# B115A.net
KiCad netlist of a schematic drawn in EAGLE
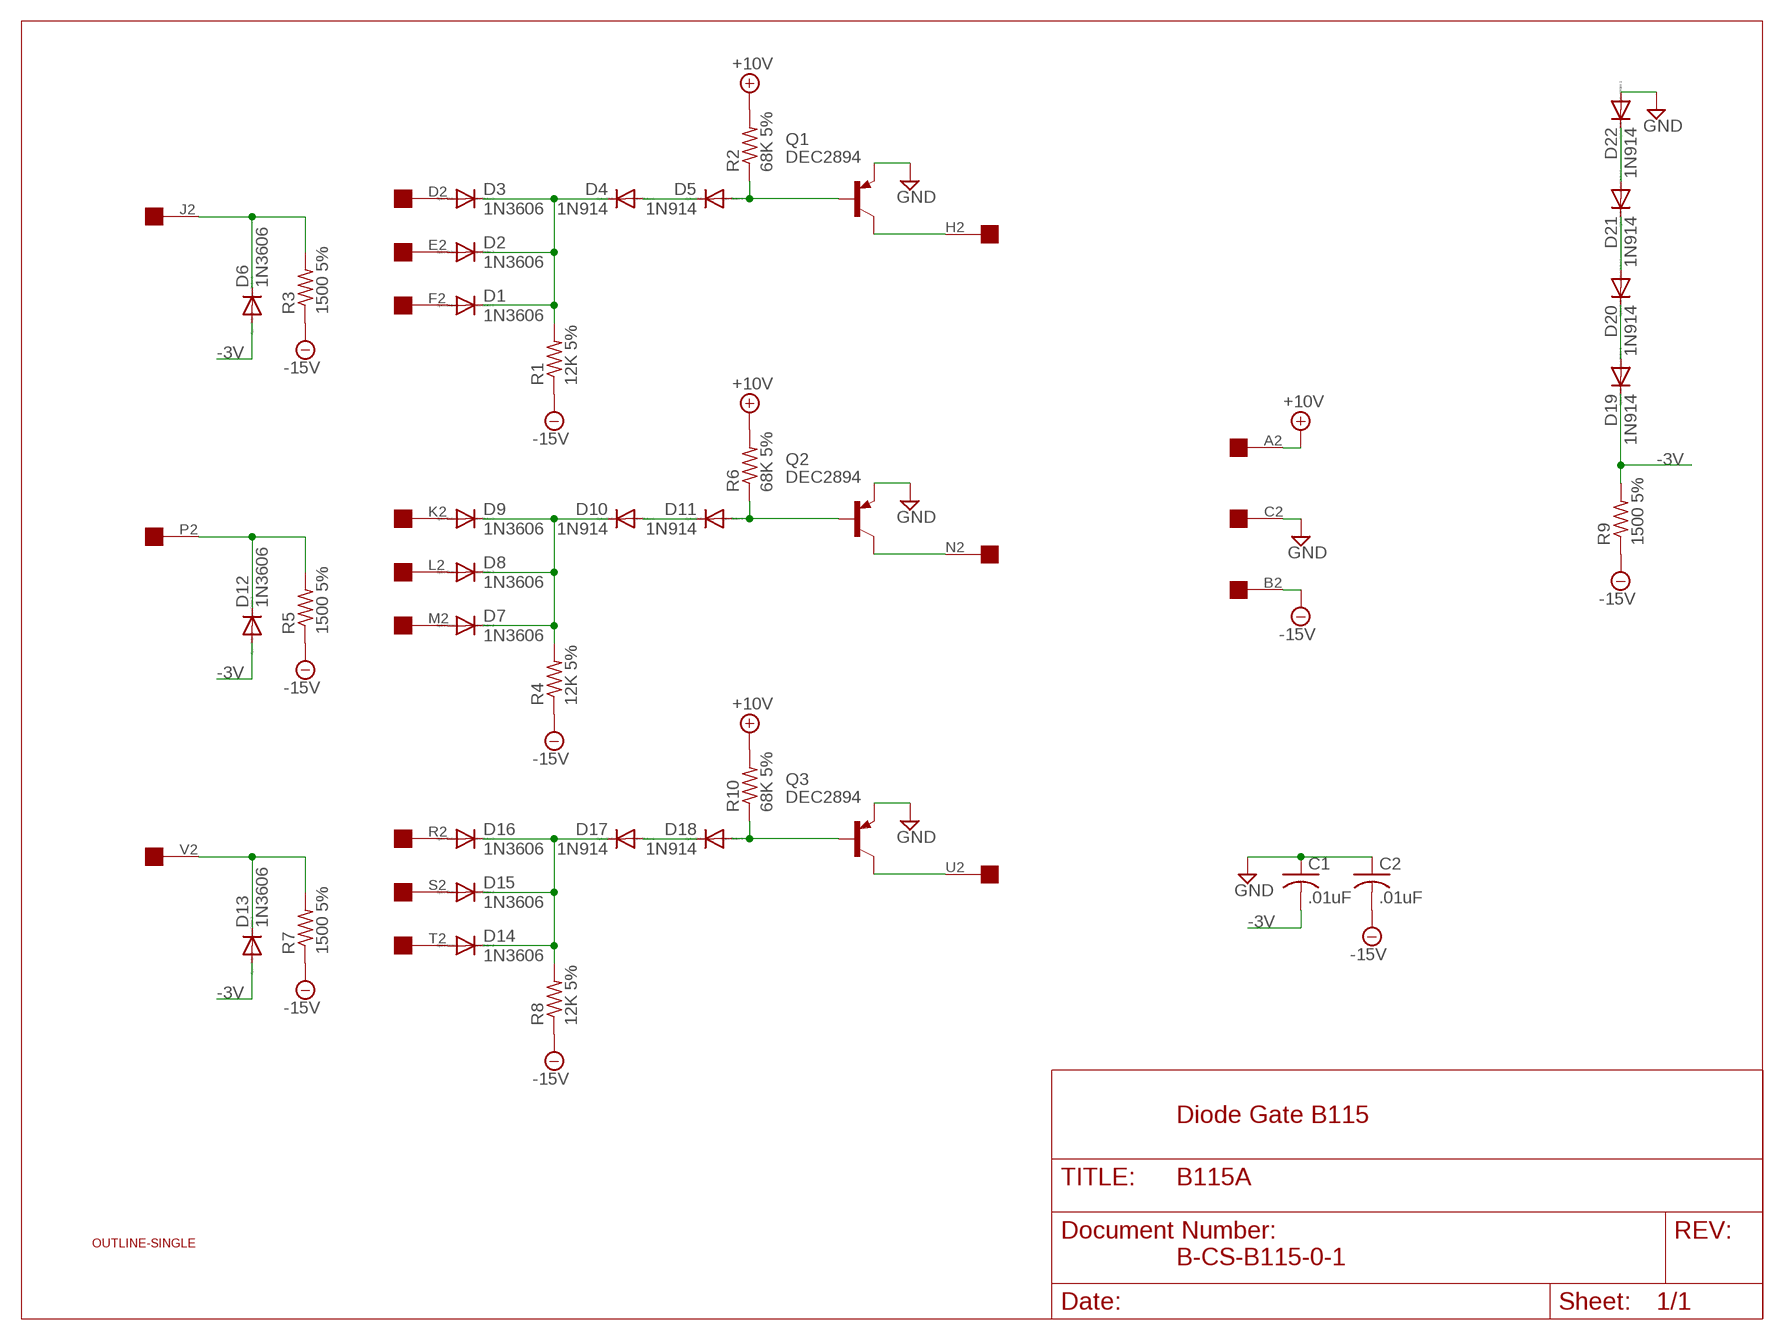
[diagram p0: schematic, sheet 1]

(export (version "E")
  (design (tool "Eeschema 10.0.6"))
  (components
    (comp (ref "C1")
      (value ".01uF")
      (footprint "eagle-import:C050-025X075")
      (libsource (lib "eagle-import") (part "C-US050-025X075"))
    )
    (comp (ref "C2")
      (value ".01uF")
      (footprint "eagle-import:C050-025X075")
      (libsource (lib "eagle-import") (part "C-US050-025X075"))
    )
    (comp (ref "D1")
      (value "1N3606")
      (footprint "eagle-import:DO35-10")
      (libsource (lib "eagle-import") (part "1N4148DO35-10"))
    )
    (comp (ref "D2")
      (value "1N3606")
      (footprint "eagle-import:DO35-10")
      (libsource (lib "eagle-import") (part "1N4148DO35-10"))
    )
    (comp (ref "D3")
      (value "1N3606")
      (footprint "eagle-import:DO35-10")
      (libsource (lib "eagle-import") (part "1N4148DO35-10"))
    )
    (comp (ref "D4")
      (value "1N914")
      (footprint "eagle-import:DO35-10")
      (libsource (lib "eagle-import") (part "1N4148DO35-10"))
    )
    (comp (ref "D5")
      (value "1N914")
      (footprint "eagle-import:DO35-10")
      (libsource (lib "eagle-import") (part "1N4148DO35-10"))
    )
    (comp (ref "D6")
      (value "1N3606")
      (footprint "eagle-import:DO35-10")
      (libsource (lib "eagle-import") (part "1N4148DO35-10"))
    )
    (comp (ref "D7")
      (value "1N3606")
      (footprint "eagle-import:DO35-10")
      (libsource (lib "eagle-import") (part "1N4148DO35-10"))
    )
    (comp (ref "D8")
      (value "1N3606")
      (footprint "eagle-import:DO35-10")
      (libsource (lib "eagle-import") (part "1N4148DO35-10"))
    )
    (comp (ref "D9")
      (value "1N3606")
      (footprint "eagle-import:DO35-10")
      (libsource (lib "eagle-import") (part "1N4148DO35-10"))
    )
    (comp (ref "D10")
      (value "1N914")
      (footprint "eagle-import:DO35-10")
      (libsource (lib "eagle-import") (part "1N4148DO35-10"))
    )
    (comp (ref "D11")
      (value "1N914")
      (footprint "eagle-import:DO35-10")
      (libsource (lib "eagle-import") (part "1N4148DO35-10"))
    )
    (comp (ref "D12")
      (value "1N3606")
      (footprint "eagle-import:DO35-10")
      (libsource (lib "eagle-import") (part "1N4148DO35-10"))
    )
    (comp (ref "D13")
      (value "1N3606")
      (footprint "eagle-import:DO35-10")
      (libsource (lib "eagle-import") (part "1N4148DO35-10"))
    )
    (comp (ref "D14")
      (value "1N3606")
      (footprint "eagle-import:DO35-10")
      (libsource (lib "eagle-import") (part "1N4148DO35-10"))
    )
    (comp (ref "D15")
      (value "1N3606")
      (footprint "eagle-import:DO35-10")
      (libsource (lib "eagle-import") (part "1N4148DO35-10"))
    )
    (comp (ref "D16")
      (value "1N3606")
      (footprint "eagle-import:DO35-10")
      (libsource (lib "eagle-import") (part "1N4148DO35-10"))
    )
    (comp (ref "D17")
      (value "1N914")
      (footprint "eagle-import:DO35-10")
      (libsource (lib "eagle-import") (part "1N4148DO35-10"))
    )
    (comp (ref "D18")
      (value "1N914")
      (footprint "eagle-import:DO35-10")
      (libsource (lib "eagle-import") (part "1N4148DO35-10"))
    )
    (comp (ref "D19")
      (value "1N914")
      (footprint "eagle-import:DO35-10")
      (libsource (lib "eagle-import") (part "1N4148DO35-10"))
    )
    (comp (ref "D20")
      (value "1N914")
      (footprint "eagle-import:DO35-10")
      (libsource (lib "eagle-import") (part "1N4148DO35-10"))
    )
    (comp (ref "D21")
      (value "1N914")
      (footprint "eagle-import:DO35-10")
      (libsource (lib "eagle-import") (part "1N4148DO35-10"))
    )
    (comp (ref "D22")
      (value "1N914")
      (footprint "eagle-import:DO35-10")
      (libsource (lib "eagle-import") (part "1N4148DO35-10"))
    )
    (comp (ref "Q1")
      (value "DEC2894")
      (footprint "eagle-import:TO39")
      (libsource (lib "eagle-import") (part "2N2904"))
    )
    (comp (ref "Q2")
      (value "DEC2894")
      (footprint "eagle-import:TO39")
      (libsource (lib "eagle-import") (part "2N2904"))
    )
    (comp (ref "Q3")
      (value "DEC2894")
      (footprint "eagle-import:TO39")
      (libsource (lib "eagle-import") (part "2N2904"))
    )
    (comp (ref "R1")
      (value "12K 5%")
      (footprint "eagle-import:0207_10")
      (libsource (lib "eagle-import") (part "R-US_0207/10"))
    )
    (comp (ref "R2")
      (value "68K 5%")
      (footprint "eagle-import:0207_10")
      (libsource (lib "eagle-import") (part "R-US_0207/10"))
    )
    (comp (ref "R3")
      (value "1500 5%")
      (footprint "eagle-import:0207_10")
      (libsource (lib "eagle-import") (part "R-US_0207/10"))
    )
    (comp (ref "R4")
      (value "12K 5%")
      (footprint "eagle-import:0207_10")
      (libsource (lib "eagle-import") (part "R-US_0207/10"))
    )
    (comp (ref "R5")
      (value "1500 5%")
      (footprint "eagle-import:0207_10")
      (libsource (lib "eagle-import") (part "R-US_0207/10"))
    )
    (comp (ref "R6")
      (value "68K 5%")
      (footprint "eagle-import:0207_10")
      (libsource (lib "eagle-import") (part "R-US_0207/10"))
    )
    (comp (ref "R7")
      (value "1500 5%")
      (footprint "eagle-import:0207_10")
      (libsource (lib "eagle-import") (part "R-US_0207/10"))
    )
    (comp (ref "R8")
      (value "12K 5%")
      (footprint "eagle-import:0207_10")
      (libsource (lib "eagle-import") (part "R-US_0207/10"))
    )
    (comp (ref "R9")
      (value "1500 5%")
      (footprint "eagle-import:0207_10")
      (libsource (lib "eagle-import") (part "R-US_0207/10"))
    )
    (comp (ref "R10")
      (value "68K 5%")
      (footprint "eagle-import:0207_10")
      (libsource (lib "eagle-import") (part "R-US_0207/10"))
    )
    (comp (ref "U$1")
      (value "OUTLINE-SINGLE")
      (footprint "eagle-import:SINGLE")
      (libsource (lib "eagle-import") (part "OUTLINE-SINGLE"))
    )
    (comp (ref "U$2")
      (value "EDGE-1")
      (footprint "eagle-import:EDGE-CON1")
      (libsource (lib "eagle-import") (part "EDGE-1"))
    )
  )
  (nets
    (net (code "1") (name "+10V") (class "Default")
      (node (ref "R10") (pin "2") (pinfunction "2_2") (pintype "passive"))
      (node (ref "R2") (pin "2") (pinfunction "2_2") (pintype "passive"))
      (node (ref "R6") (pin "2") (pinfunction "2_2") (pintype "passive"))
      (node (ref "U$2") (pin "A2") (pinfunction "1_A2") (pintype "bidirectional"))
    )
    (net (code "2") (name "-15V") (class "Default")
      (node (ref "C2") (pin "2") (pinfunction "2_2") (pintype "passive"))
      (node (ref "R1") (pin "1") (pinfunction "1_1") (pintype "passive"))
      (node (ref "R3") (pin "1") (pinfunction "1_1") (pintype "passive"))
      (node (ref "R4") (pin "1") (pinfunction "1_1") (pintype "passive"))
      (node (ref "R5") (pin "1") (pinfunction "1_1") (pintype "passive"))
      (node (ref "R7") (pin "1") (pinfunction "1_1") (pintype "passive"))
      (node (ref "R8") (pin "1") (pinfunction "1_1") (pintype "passive"))
      (node (ref "R9") (pin "1") (pinfunction "1_1") (pintype "passive"))
      (node (ref "U$2") (pin "B2") (pinfunction "1_B2") (pintype "bidirectional"))
    )
    (net (code "3") (name "/-3V") (class "Default")
      (node (ref "C1") (pin "2") (pinfunction "2_2") (pintype "passive"))
      (node (ref "D12") (pin "A") (pinfunction "A_A") (pintype "passive"))
      (node (ref "D13") (pin "A") (pinfunction "A_A") (pintype "passive"))
      (node (ref "D19") (pin "C") (pinfunction "C_C") (pintype "passive"))
      (node (ref "D6") (pin "A") (pinfunction "A_A") (pintype "passive"))
      (node (ref "R9") (pin "2") (pinfunction "2_2") (pintype "passive"))
    )
    (net (code "4") (name "GND") (class "Default")
      (node (ref "C1") (pin "1") (pinfunction "1_1") (pintype "passive"))
      (node (ref "C2") (pin "1") (pinfunction "1_1") (pintype "passive"))
      (node (ref "D22") (pin "A") (pinfunction "A_A") (pintype "passive"))
      (node (ref "Q1") (pin "1") (pinfunction "E_1") (pintype "passive"))
      (node (ref "Q2") (pin "1") (pinfunction "E_1") (pintype "passive"))
      (node (ref "Q3") (pin "1") (pinfunction "E_1") (pintype "passive"))
      (node (ref "U$2") (pin "C2") (pinfunction "1_C2") (pintype "bidirectional"))
    )
    (net (code "5") (name "Net-(D1-PadC)") (class "Default")
      (node (ref "D1") (pin "C") (pinfunction "C_C") (pintype "passive"))
      (node (ref "D2") (pin "C") (pinfunction "C_C") (pintype "passive"))
      (node (ref "D3") (pin "C") (pinfunction "C_C") (pintype "passive"))
      (node (ref "D4") (pin "C") (pinfunction "C_C") (pintype "passive"))
      (node (ref "R1") (pin "2") (pinfunction "2_2") (pintype "passive"))
    )
    (net (code "6") (name "Net-(D4-PadA)") (class "Default")
      (node (ref "D4") (pin "A") (pinfunction "A_A") (pintype "passive"))
      (node (ref "D5") (pin "C") (pinfunction "C_C") (pintype "passive"))
    )
    (net (code "7") (name "Net-(D10-PadA)") (class "Default")
      (node (ref "D10") (pin "A") (pinfunction "A_A") (pintype "passive"))
      (node (ref "D11") (pin "C") (pinfunction "C_C") (pintype "passive"))
    )
    (net (code "8") (name "Net-(D10-PadC)") (class "Default")
      (node (ref "D10") (pin "C") (pinfunction "C_C") (pintype "passive"))
      (node (ref "D7") (pin "C") (pinfunction "C_C") (pintype "passive"))
      (node (ref "D8") (pin "C") (pinfunction "C_C") (pintype "passive"))
      (node (ref "D9") (pin "C") (pinfunction "C_C") (pintype "passive"))
      (node (ref "R4") (pin "2") (pinfunction "2_2") (pintype "passive"))
    )
    (net (code "9") (name "Net-(D14-PadC)") (class "Default")
      (node (ref "D14") (pin "C") (pinfunction "C_C") (pintype "passive"))
      (node (ref "D15") (pin "C") (pinfunction "C_C") (pintype "passive"))
      (node (ref "D16") (pin "C") (pinfunction "C_C") (pintype "passive"))
      (node (ref "D17") (pin "C") (pinfunction "C_C") (pintype "passive"))
      (node (ref "R8") (pin "2") (pinfunction "2_2") (pintype "passive"))
    )
    (net (code "10") (name "Net-(D17-PadA)") (class "Default")
      (node (ref "D17") (pin "A") (pinfunction "A_A") (pintype "passive"))
      (node (ref "D18") (pin "C") (pinfunction "C_C") (pintype "passive"))
    )
    (net (code "11") (name "Net-(D19-PadA)") (class "Default")
      (node (ref "D19") (pin "A") (pinfunction "A_A") (pintype "passive"))
      (node (ref "D20") (pin "C") (pinfunction "C_C") (pintype "passive"))
    )
    (net (code "12") (name "Net-(D20-PadA)") (class "Default")
      (node (ref "D20") (pin "A") (pinfunction "A_A") (pintype "passive"))
      (node (ref "D21") (pin "C") (pinfunction "C_C") (pintype "passive"))
    )
    (net (code "13") (name "Net-(D21-PadA)") (class "Default")
      (node (ref "D21") (pin "A") (pinfunction "A_A") (pintype "passive"))
      (node (ref "D22") (pin "C") (pinfunction "C_C") (pintype "passive"))
    )
    (net (code "14") (name "Net-(Q1-B)") (class "Default")
      (node (ref "D5") (pin "A") (pinfunction "A_A") (pintype "passive"))
      (node (ref "Q1") (pin "2") (pinfunction "B_2") (pintype "passive"))
      (node (ref "R2") (pin "1") (pinfunction "1_1") (pintype "passive"))
    )
    (net (code "15") (name "Net-(Q1-C)") (class "Default")
      (node (ref "Q1") (pin "3") (pinfunction "C_3") (pintype "passive"))
      (node (ref "U$2") (pin "H2") (pinfunction "1_H2") (pintype "bidirectional"))
    )
    (net (code "16") (name "Net-(Q2-B)") (class "Default")
      (node (ref "D11") (pin "A") (pinfunction "A_A") (pintype "passive"))
      (node (ref "Q2") (pin "2") (pinfunction "B_2") (pintype "passive"))
      (node (ref "R6") (pin "1") (pinfunction "1_1") (pintype "passive"))
    )
    (net (code "17") (name "Net-(Q2-C)") (class "Default")
      (node (ref "Q2") (pin "3") (pinfunction "C_3") (pintype "passive"))
      (node (ref "U$2") (pin "N2") (pinfunction "1_N2") (pintype "bidirectional"))
    )
    (net (code "18") (name "Net-(Q3-B)") (class "Default")
      (node (ref "D18") (pin "A") (pinfunction "A_A") (pintype "passive"))
      (node (ref "Q3") (pin "2") (pinfunction "B_2") (pintype "passive"))
      (node (ref "R10") (pin "1") (pinfunction "1_1") (pintype "passive"))
    )
    (net (code "19") (name "Net-(Q3-C)") (class "Default")
      (node (ref "Q3") (pin "3") (pinfunction "C_3") (pintype "passive"))
      (node (ref "U$2") (pin "U2") (pinfunction "1_U2") (pintype "bidirectional"))
    )
    (net (code "20") (name "Net-(U$2D-1)") (class "Default")
      (node (ref "D3") (pin "A") (pinfunction "A_A") (pintype "passive"))
      (node (ref "U$2") (pin "D2") (pinfunction "1_D2") (pintype "bidirectional"))
    )
    (net (code "21") (name "Net-(U$2E-1)") (class "Default")
      (node (ref "D2") (pin "A") (pinfunction "A_A") (pintype "passive"))
      (node (ref "U$2") (pin "E2") (pinfunction "1_E2") (pintype "bidirectional"))
    )
    (net (code "22") (name "Net-(U$2F-1)") (class "Default")
      (node (ref "D1") (pin "A") (pinfunction "A_A") (pintype "passive"))
      (node (ref "U$2") (pin "F2") (pinfunction "1_F2") (pintype "bidirectional"))
    )
    (net (code "23") (name "Net-(U$2H-1)") (class "Default")
      (node (ref "D6") (pin "C") (pinfunction "C_C") (pintype "passive"))
      (node (ref "R3") (pin "2") (pinfunction "2_2") (pintype "passive"))
      (node (ref "U$2") (pin "J2") (pinfunction "1_J2") (pintype "bidirectional"))
    )
    (net (code "24") (name "Net-(U$2I-1)") (class "Default")
      (node (ref "D9") (pin "A") (pinfunction "A_A") (pintype "passive"))
      (node (ref "U$2") (pin "K2") (pinfunction "1_K2") (pintype "bidirectional"))
    )
    (net (code "25") (name "Net-(U$2J-1)") (class "Default")
      (node (ref "D8") (pin "A") (pinfunction "A_A") (pintype "passive"))
      (node (ref "U$2") (pin "L2") (pinfunction "1_L2") (pintype "bidirectional"))
    )
    (net (code "26") (name "Net-(U$2K-1)") (class "Default")
      (node (ref "D7") (pin "A") (pinfunction "A_A") (pintype "passive"))
      (node (ref "U$2") (pin "M2") (pinfunction "1_M2") (pintype "bidirectional"))
    )
    (net (code "27") (name "Net-(U$2M-1)") (class "Default")
      (node (ref "D12") (pin "C") (pinfunction "C_C") (pintype "passive"))
      (node (ref "R5") (pin "2") (pinfunction "2_2") (pintype "passive"))
      (node (ref "U$2") (pin "P2") (pinfunction "1_P2") (pintype "bidirectional"))
    )
    (net (code "28") (name "Net-(U$2N-1)") (class "Default")
      (node (ref "D16") (pin "A") (pinfunction "A_A") (pintype "passive"))
      (node (ref "U$2") (pin "R2") (pinfunction "1_R2") (pintype "bidirectional"))
    )
    (net (code "29") (name "Net-(U$2O-1)") (class "Default")
      (node (ref "D15") (pin "A") (pinfunction "A_A") (pintype "passive"))
      (node (ref "U$2") (pin "S2") (pinfunction "1_S2") (pintype "bidirectional"))
    )
    (net (code "30") (name "Net-(U$2P-1)") (class "Default")
      (node (ref "D14") (pin "A") (pinfunction "A_A") (pintype "passive"))
      (node (ref "U$2") (pin "T2") (pinfunction "1_T2") (pintype "bidirectional"))
    )
    (net (code "31") (name "Net-(U$2R-1)") (class "Default")
      (node (ref "D13") (pin "C") (pinfunction "C_C") (pintype "passive"))
      (node (ref "R7") (pin "2") (pinfunction "2_2") (pintype "passive"))
      (node (ref "U$2") (pin "V2") (pinfunction "1_V2") (pintype "bidirectional"))
    )
  )
)
